# circuit.net
KiCad netlist of a schematic drawn in EAGLE
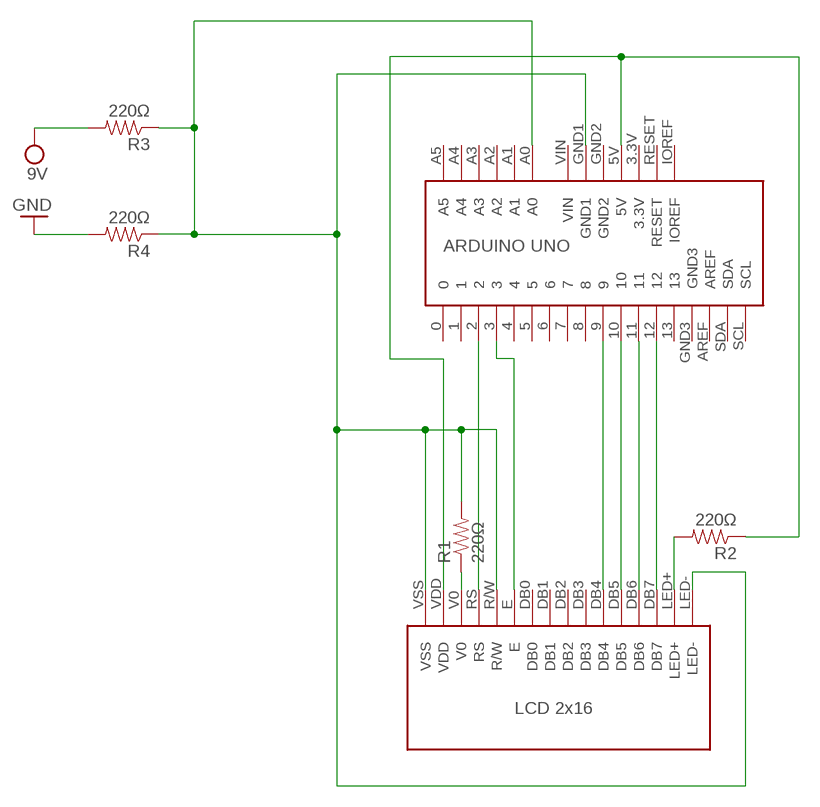
[diagram p0: schematic, sheet 1]

(export (version "E")
  (design (tool "Eeschema 10.0.6"))
  (components
    (comp (ref "R1")
      (value "220Ω")
      (footprint "eagle-import:0402-RES")
      (libsource (lib "eagle-import") (part "RESISTOR0402"))
    )
    (comp (ref "R2")
      (value "220Ω")
      (footprint "eagle-import:0402-RES")
      (libsource (lib "eagle-import") (part "RESISTOR0402"))
    )
    (comp (ref "R3")
      (value "220Ω")
      (footprint "eagle-import:0402-RES")
      (libsource (lib "eagle-import") (part "RESISTOR0402"))
    )
    (comp (ref "R4")
      (value "220Ω")
      (footprint "eagle-import:0402-RES")
      (libsource (lib "eagle-import") (part "RESISTOR0402"))
    )
    (comp (ref "U$1")
      (value "LCD_2_16")
      (footprint "eagle-import:LCD_2_16")
      (libsource (lib "eagle-import") (part "LCD_2_16"))
    )
    (comp (ref "U$2")
      (value "ARDUINO_UNO")
      (footprint "eagle-import:ARDUINO_UNO")
      (libsource (lib "eagle-import") (part "ARDUINO_UNO"))
    )
  )
  (nets
    (net (code "1") (name "9V") (class "Default")
      (node (ref "R3") (pin "2") (pinfunction "2_2") (pintype "passive"))
    )
    (net (code "2") (name "GND") (class "Default")
      (node (ref "R4") (pin "2") (pinfunction "2_2") (pintype "passive"))
    )
    (net (code "3") (name "Net-(R1-Pad1)") (class "Default")
      (node (ref "R1") (pin "1") (pinfunction "1_1") (pintype "passive"))
      (node (ref "U$1") (pin "V0") (pinfunction "V0_V0") (pintype "bidirectional"))
    )
    (net (code "4") (name "Net-(R1-Pad2)") (class "Default")
      (node (ref "R1") (pin "2") (pinfunction "2_2") (pintype "passive"))
      (node (ref "R3") (pin "1") (pinfunction "1_1") (pintype "passive"))
      (node (ref "R4") (pin "1") (pinfunction "1_1") (pintype "passive"))
      (node (ref "U$1") (pin "LED-") (pinfunction "LED-_LED-") (pintype "bidirectional"))
      (node (ref "U$1") (pin "R/W") (pinfunction "R/W_R/W") (pintype "bidirectional"))
      (node (ref "U$1") (pin "VSS") (pinfunction "VSS_VSS") (pintype "bidirectional"))
      (node (ref "U$2") (pin "A0") (pinfunction "A0_A0") (pintype "bidirectional"))
      (node (ref "U$2") (pin "GND1") (pinfunction "GND1_GND1") (pintype "bidirectional"))
    )
    (net (code "5") (name "Net-(R2-Pad1)") (class "Default")
      (node (ref "R2") (pin "1") (pinfunction "1_1") (pintype "passive"))
      (node (ref "U$1") (pin "VDD") (pinfunction "VDD_VDD") (pintype "bidirectional"))
      (node (ref "U$2") (pin "5V") (pinfunction "5V_5V") (pintype "bidirectional"))
    )
    (net (code "6") (name "Net-(R2-Pad2)") (class "Default")
      (node (ref "R2") (pin "2") (pinfunction "2_2") (pintype "passive"))
      (node (ref "U$1") (pin "LED+") (pinfunction "LED+_LED+") (pintype "bidirectional"))
    )
    (net (code "7") (name "Net-(U$1-PadDB4)") (class "Default")
      (node (ref "U$1") (pin "DB4") (pinfunction "DB4_DB4") (pintype "bidirectional"))
      (node (ref "U$2") (pin "9") (pinfunction "9_9") (pintype "bidirectional"))
    )
    (net (code "8") (name "Net-(U$1-PadDB5)") (class "Default")
      (node (ref "U$1") (pin "DB5") (pinfunction "DB5_DB5") (pintype "bidirectional"))
      (node (ref "U$2") (pin "10") (pinfunction "10_10") (pintype "bidirectional"))
    )
    (net (code "9") (name "Net-(U$1-PadDB6)") (class "Default")
      (node (ref "U$1") (pin "DB6") (pinfunction "DB6_DB6") (pintype "bidirectional"))
      (node (ref "U$2") (pin "11") (pinfunction "11_11") (pintype "bidirectional"))
    )
    (net (code "10") (name "Net-(U$1-PadDB7)") (class "Default")
      (node (ref "U$1") (pin "DB7") (pinfunction "DB7_DB7") (pintype "bidirectional"))
      (node (ref "U$2") (pin "12") (pinfunction "12_12") (pintype "bidirectional"))
    )
    (net (code "11") (name "Net-(U$1-PadE)") (class "Default")
      (node (ref "U$1") (pin "E") (pinfunction "E_E") (pintype "bidirectional"))
      (node (ref "U$2") (pin "3") (pinfunction "3_3") (pintype "bidirectional"))
    )
    (net (code "12") (name "Net-(U$1-PadRS)") (class "Default")
      (node (ref "U$1") (pin "RS") (pinfunction "RS_RS") (pintype "bidirectional"))
      (node (ref "U$2") (pin "2") (pinfunction "2_2") (pintype "bidirectional"))
    )
    (net (code "13") (name "unconnected-(U$1-PadDB0)") (class "Default")
      (node (ref "U$1") (pin "DB0") (pinfunction "DB0_DB0") (pintype "bidirectional"))
    )
    (net (code "14") (name "unconnected-(U$1-PadDB1)") (class "Default")
      (node (ref "U$1") (pin "DB1") (pinfunction "DB1_DB1") (pintype "bidirectional"))
    )
    (net (code "15") (name "unconnected-(U$1-PadDB2)") (class "Default")
      (node (ref "U$1") (pin "DB2") (pinfunction "DB2_DB2") (pintype "bidirectional"))
    )
    (net (code "16") (name "unconnected-(U$1-PadDB3)") (class "Default")
      (node (ref "U$1") (pin "DB3") (pinfunction "DB3_DB3") (pintype "bidirectional"))
    )
    (net (code "17") (name "unconnected-(U$2-Pad0)") (class "Default")
      (node (ref "U$2") (pin "0") (pinfunction "0_0") (pintype "bidirectional"))
    )
    (net (code "18") (name "unconnected-(U$2-Pad1)") (class "Default")
      (node (ref "U$2") (pin "1") (pinfunction "1_1") (pintype "bidirectional"))
    )
    (net (code "19") (name "unconnected-(U$2-Pad3.3V)") (class "Default")
      (node (ref "U$2") (pin "3.3V") (pinfunction "3.3V_3.3V") (pintype "bidirectional"))
    )
    (net (code "20") (name "unconnected-(U$2-Pad4)") (class "Default")
      (node (ref "U$2") (pin "4") (pinfunction "4_4") (pintype "bidirectional"))
    )
    (net (code "21") (name "unconnected-(U$2-Pad5)") (class "Default")
      (node (ref "U$2") (pin "5") (pinfunction "5_5") (pintype "bidirectional"))
    )
    (net (code "22") (name "unconnected-(U$2-Pad6)") (class "Default")
      (node (ref "U$2") (pin "6") (pinfunction "6_6") (pintype "bidirectional"))
    )
    (net (code "23") (name "unconnected-(U$2-Pad7)") (class "Default")
      (node (ref "U$2") (pin "7") (pinfunction "7_7") (pintype "bidirectional"))
    )
    (net (code "24") (name "unconnected-(U$2-Pad8)") (class "Default")
      (node (ref "U$2") (pin "8") (pinfunction "8_8") (pintype "bidirectional"))
    )
    (net (code "25") (name "unconnected-(U$2-Pad13)") (class "Default")
      (node (ref "U$2") (pin "13") (pinfunction "13_13") (pintype "bidirectional"))
    )
    (net (code "26") (name "unconnected-(U$2-PadA1)") (class "Default")
      (node (ref "U$2") (pin "A1") (pinfunction "A1_A1") (pintype "bidirectional"))
    )
    (net (code "27") (name "unconnected-(U$2-PadA2)") (class "Default")
      (node (ref "U$2") (pin "A2") (pinfunction "A2_A2") (pintype "bidirectional"))
    )
    (net (code "28") (name "unconnected-(U$2-PadA3)") (class "Default")
      (node (ref "U$2") (pin "A3") (pinfunction "A3_A3") (pintype "bidirectional"))
    )
    (net (code "29") (name "unconnected-(U$2-PadA4)") (class "Default")
      (node (ref "U$2") (pin "A4") (pinfunction "A4_A4") (pintype "bidirectional"))
    )
    (net (code "30") (name "unconnected-(U$2-PadA5)") (class "Default")
      (node (ref "U$2") (pin "A5") (pinfunction "A5_A5") (pintype "bidirectional"))
    )
    (net (code "31") (name "unconnected-(U$2-PadAREF)") (class "Default")
      (node (ref "U$2") (pin "AREF") (pinfunction "AREF_AREF") (pintype "bidirectional"))
    )
    (net (code "32") (name "unconnected-(U$2-PadGND2)") (class "Default")
      (node (ref "U$2") (pin "GND2") (pinfunction "GND2_GND2") (pintype "bidirectional"))
    )
    (net (code "33") (name "unconnected-(U$2-PadGND3)") (class "Default")
      (node (ref "U$2") (pin "GND3") (pinfunction "GND3_GND3") (pintype "bidirectional"))
    )
    (net (code "34") (name "unconnected-(U$2-PadIOREF)") (class "Default")
      (node (ref "U$2") (pin "IOREF") (pinfunction "IOREF_IOREF") (pintype "bidirectional"))
    )
    (net (code "35") (name "unconnected-(U$2-PadRESET)") (class "Default")
      (node (ref "U$2") (pin "RESET") (pinfunction "RESET_RESET") (pintype "bidirectional"))
    )
    (net (code "36") (name "unconnected-(U$2-PadSCL)") (class "Default")
      (node (ref "U$2") (pin "SCL") (pinfunction "SCL_SCL") (pintype "bidirectional"))
    )
    (net (code "37") (name "unconnected-(U$2-PadSDA)") (class "Default")
      (node (ref "U$2") (pin "SDA") (pinfunction "SDA_SDA") (pintype "bidirectional"))
    )
    (net (code "38") (name "unconnected-(U$2-PadVIN)") (class "Default")
      (node (ref "U$2") (pin "VIN") (pinfunction "VIN_VIN") (pintype "bidirectional"))
    )
  )
)
